# Mosfet_Driver_Circuit.net
KiCad netlist of a schematic drawn in Altium Designer
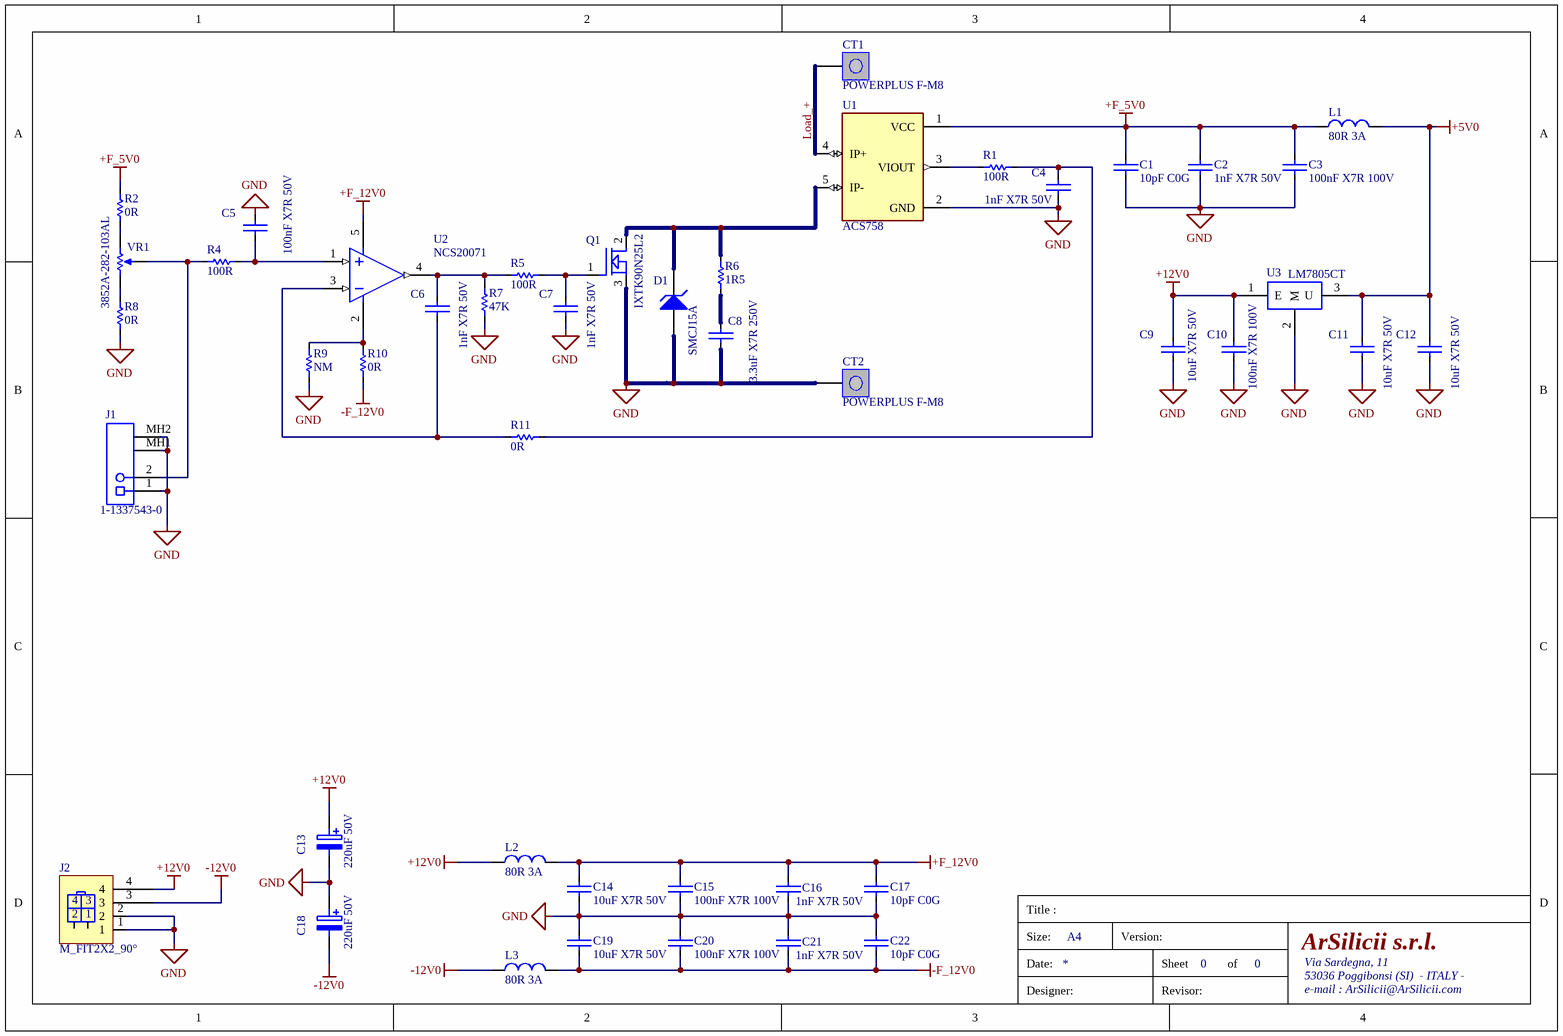
[diagram p0: Mosfet_Driver_Circuit.SchDoc]

(export (version "E")
  (design (tool "Eeschema 10.0.6"))
  (components
    (comp (ref "C1")
      (value "10pF C0G")
      (footprint "0805")
      (description "Capacità")
      (fields (field (name "ARSILICII PART NUMBER") "CPC0614010"))
      (libsource (lib "Library_20-02-20") (part "CAP_10pF C0G_0805"))
    )
    (comp (ref "C2")
      (value "1nF X7R 50V")
      (footprint "0805")
      (description "Capacità")
      (fields
        (field (name "1 SUPPLIER PART NUMBER") "B37941K5102K60")
        (field (name "2 SUPPLIER PART NUMBER") "0805B102K5CT")
      )
      (libsource (lib "Library_20-02-20") (part "CAP_1nF X7R 50V_0805"))
    )
    (comp (ref "C3")
      (value "100nF X7R 100V")
      (footprint "0805")
      (description "Capacità")
      (fields
        (field (name "1 SUPPLIER PART NUMBER") "CL21B104KCFSFNG")
        (field (name "2 SUPPLIER PART NUMBER") "1907331")
      )
      (libsource (lib "Library_20-02-20") (part "CAP_100nF X7R 100V_0805"))
    )
    (comp (ref "C4")
      (value "1nF X7R 50V")
      (footprint "0805")
      (description "Capacità")
      (fields
        (field (name "1 SUPPLIER PART NUMBER") "B37941K5102K60")
        (field (name "2 SUPPLIER PART NUMBER") "0805B102K5CT")
      )
      (libsource (lib "Library_20-02-20") (part "CAP_1nF X7R 50V_0805"))
    )
    (comp (ref "C5")
      (value "100nF X7R 50V")
      (footprint "0805")
      (description "Capacità")
      (fields
        (field (name "1 SUPPLIER PART NUMBER") "C0805C104K5RAC7800")
        (field (name "2 SUPPLIER PART NUMBER") "08055C104KAT2A AVX")
      )
      (libsource (lib "Library_20-02-20") (part "CAP_100nF X7R 50V_0805"))
    )
    (comp (ref "C6")
      (value "1nF X7R 50V")
      (footprint "0805")
      (description "Capacità")
      (fields
        (field (name "1 SUPPLIER PART NUMBER") "B37941K5102K60")
        (field (name "2 SUPPLIER PART NUMBER") "0805B102K5CT")
      )
      (libsource (lib "Library_20-02-20") (part "CAP_1nF X7R 50V_0805"))
    )
    (comp (ref "C7")
      (value "1nF X7R 50V")
      (footprint "0805")
      (description "Capacità")
      (fields
        (field (name "1 SUPPLIER PART NUMBER") "B37941K5102K60")
        (field (name "2 SUPPLIER PART NUMBER") "0805B102K5CT")
      )
      (libsource (lib "Library_20-02-20") (part "CAP_1nF X7R 50V_0805"))
    )
    (comp (ref "C8")
      (value "3.3uF X7R 250V")
      (footprint "2220")
      (description "Capacità")
      (fields
        (field (name "1 SUPPLIER PART NUMBER") "2435506")
        (field (name "2 SUPPLIER PART NUMBER") "810-CGA9N3X7R2E105K")
      )
      (libsource (lib "Library_20-02-20") (part "CAP_1uF X7R 250V_2220"))
    )
    (comp (ref "C9")
      (value "10uF X7R 50V")
      (footprint "1206")
      (description "Capacità")
      (fields
        (field (name "1 SUPPLIER PART NUMBER") "CL31B106KBHNNNE")
        (field (name "ARSILICII PART NUMBER") "CPC0232011")
      )
      (libsource (lib "Library_20-02-20") (part "CAP_10uF X7R 50V_1206"))
    )
    (comp (ref "C10")
      (value "100nF X7R 100V")
      (footprint "0805")
      (description "Capacità")
      (fields
        (field (name "1 SUPPLIER PART NUMBER") "CL21B104KCFSFNG")
        (field (name "2 SUPPLIER PART NUMBER") "1907331")
      )
      (libsource (lib "Library_20-02-20") (part "CAP_100nF X7R 100V_0805"))
    )
    (comp (ref "C11")
      (value "10uF X7R 50V")
      (footprint "1206")
      (description "Capacità")
      (fields
        (field (name "1 SUPPLIER PART NUMBER") "CL31B106KBHNNNE")
        (field (name "ARSILICII PART NUMBER") "CPC0232011")
      )
      (libsource (lib "Library_20-02-20") (part "CAP_10uF X7R 50V_1206"))
    )
    (comp (ref "C12")
      (value "10uF X7R 50V")
      (footprint "1206")
      (description "Capacità")
      (fields
        (field (name "1 SUPPLIER PART NUMBER") "CL31B106KBHNNNE")
        (field (name "ARSILICII PART NUMBER") "CPC0232011")
      )
      (libsource (lib "Library_20-02-20") (part "CAP_10uF X7R 50V_1206"))
    )
    (comp (ref "C13")
      (value "220uF 50V")
      (footprint "C_G55")
      (description "Capacità polarizzata")
      (fields
        (field (name "2 SUPPLIER PART NUMBER") "5194346")
        (field (name "ARSILICII PART NUMBER") "CPC0402221")
      )
      (libsource (lib "Library_20-02-20") (part "CAP_EL_220uF 50V"))
    )
    (comp (ref "C14")
      (value "10uF X7R 50V")
      (footprint "1206")
      (description "Capacità")
      (fields
        (field (name "1 SUPPLIER PART NUMBER") "CL31B106KBHNNNE")
        (field (name "ARSILICII PART NUMBER") "CPC0232011")
      )
      (libsource (lib "Library_20-02-20") (part "CAP_10uF X7R 50V_1206"))
    )
    (comp (ref "C15")
      (value "100nF X7R 100V")
      (footprint "0805")
      (description "Capacità")
      (fields
        (field (name "1 SUPPLIER PART NUMBER") "CL21B104KCFSFNG")
        (field (name "2 SUPPLIER PART NUMBER") "1907331")
      )
      (libsource (lib "Library_20-02-20") (part "CAP_100nF X7R 100V_0805"))
    )
    (comp (ref "C16")
      (value "1nF X7R 50V")
      (footprint "0805")
      (description "Capacità")
      (fields
        (field (name "1 SUPPLIER PART NUMBER") "B37941K5102K60")
        (field (name "2 SUPPLIER PART NUMBER") "0805B102K5CT")
      )
      (libsource (lib "Library_20-02-20") (part "CAP_1nF X7R 50V_0805"))
    )
    (comp (ref "C17")
      (value "10pF C0G")
      (footprint "0805")
      (description "Capacità")
      (fields (field (name "ARSILICII PART NUMBER") "CPC0614010"))
      (libsource (lib "Library_20-02-20") (part "CAP_10pF C0G_0805"))
    )
    (comp (ref "C18")
      (value "220uF 50V")
      (footprint "C_G55")
      (description "Capacità polarizzata")
      (fields
        (field (name "2 SUPPLIER PART NUMBER") "5194346")
        (field (name "ARSILICII PART NUMBER") "CPC0402221")
      )
      (libsource (lib "Library_20-02-20") (part "CAP_EL_220uF 50V"))
    )
    (comp (ref "C19")
      (value "10uF X7R 50V")
      (footprint "1206")
      (description "Capacità")
      (fields
        (field (name "1 SUPPLIER PART NUMBER") "CL31B106KBHNNNE")
        (field (name "ARSILICII PART NUMBER") "CPC0232011")
      )
      (libsource (lib "Library_20-02-20") (part "CAP_10uF X7R 50V_1206"))
    )
    (comp (ref "C20")
      (value "100nF X7R 100V")
      (footprint "0805")
      (description "Capacità")
      (fields
        (field (name "1 SUPPLIER PART NUMBER") "CL21B104KCFSFNG")
        (field (name "2 SUPPLIER PART NUMBER") "1907331")
      )
      (libsource (lib "Library_20-02-20") (part "CAP_100nF X7R 100V_0805"))
    )
    (comp (ref "C21")
      (value "1nF X7R 50V")
      (footprint "0805")
      (description "Capacità")
      (fields
        (field (name "1 SUPPLIER PART NUMBER") "B37941K5102K60")
        (field (name "2 SUPPLIER PART NUMBER") "0805B102K5CT")
      )
      (libsource (lib "Library_20-02-20") (part "CAP_1nF X7R 50V_0805"))
    )
    (comp (ref "C22")
      (value "10pF C0G")
      (footprint "0805")
      (description "Capacità")
      (fields (field (name "ARSILICII PART NUMBER") "CPC0614010"))
      (libsource (lib "Library_20-02-20") (part "CAP_10pF C0G_0805"))
    )
    (comp (ref "CT1")
      (value "POWERPLUS F-M8")
      (footprint "PowerPlus M8")
      (description "Singolo contatto")
      (fields
        (field (name "1 SUPPLIER PART NUMBER") "S98978")
        (field (name "ARSILICII PART NUMBER") "QC04000180")
      )
      (libsource (lib "Library_20-02-20") (part "PAD_POWERPLUS F-M8"))
    )
    (comp (ref "CT2")
      (value "POWERPLUS F-M8")
      (footprint "PowerPlus M8")
      (description "Singolo contatto")
      (fields
        (field (name "1 SUPPLIER PART NUMBER") "S98978")
        (field (name "ARSILICII PART NUMBER") "QC04000180")
      )
      (libsource (lib "Library_20-02-20") (part "PAD_POWERPLUS F-M8"))
    )
    (comp (ref "D1")
      (value "SMCJ15A")
      (footprint "LFUS-DO-214AB-2_V")
      (fields (field (name "MANUFACTURER") "Littelfuse"))
      (libsource (lib "Altium Content Vault") (part "DZEN-AK-2"))
    )
    (comp (ref "J1")
      (value "1-1337543-0")
      (footprint "TECO-1-1337543-0_V")
      (fields (field (name "MANUFACTURER") "TE Connectivity"))
      (libsource (lib "Altium Content Vault") (part "CN-1P-F-R2_A"))
    )
    (comp (ref "J2")
      (value "M_FIT2X2_90°")
      (footprint "M_FIT_JR2X2")
      (description "Mini Fit Junior 4 poli")
      (fields
        (field (name "3 SUPPLIER PART NUMBER") "C4255WR-2X2P")
        (field (name "ARSILICII PART NUMBER") "QA02001000")
      )
      (libsource (lib "ArS_Library") (part "M_FIT2X2_90°"))
    )
    (comp (ref "L1")
      (value "80R 3A")
      (footprint "1206")
      (description "Ferrite")
      (fields
        (field (name "1 SUPPLIER PART NUMBER") "3275550P")
        (field (name "ARSILICII PART NUMBER") "CPF0006000")
      )
      (libsource (lib "") (part "Ferrite 80R 3A_1"))
    )
    (comp (ref "L2")
      (value "80R 3A")
      (footprint "1206")
      (description "Ferrite")
      (fields
        (field (name "1 SUPPLIER PART NUMBER") "3275550P")
        (field (name "ARSILICII PART NUMBER") "CPF0006000")
      )
      (libsource (lib "Library_20-02-20") (part "Ferrite 80R 3A"))
    )
    (comp (ref "L3")
      (value "80R 3A")
      (footprint "1206")
      (description "Ferrite")
      (fields
        (field (name "1 SUPPLIER PART NUMBER") "3275550P")
        (field (name "ARSILICII PART NUMBER") "CPF0006000")
      )
      (libsource (lib "Library_20-02-20") (part "Ferrite 80R 3A"))
    )
    (comp (ref "Q1")
      (value "IXTK90N25L2")
      (footprint "Library_20-02-20:TO-247")
      (description "MOS CANALE N-250V-90A Linear")
      (fields
        (field (name "1 SUPPLIER PART NUMBER") "PB90N06S4-04")
        (field (name "2 SUPPLIER PART NUMBER") "826-9042P")
      )
      (libsource (lib "Library_20-02-20") (part "IXTK90N25L2"))
    )
    (comp (ref "R1")
      (value "100R")
      (footprint "0805")
      (description "Resistenza")
      (libsource (lib "Library_20-02-20") (part "RES_SMD"))
    )
    (comp (ref "R2")
      (value "0R")
      (footprint "0805")
      (description "Resistenza")
      (libsource (lib "Library_20-02-20") (part "RES_SMD"))
    )
    (comp (ref "R4")
      (value "100R")
      (footprint "0805")
      (description "Resistenza")
      (libsource (lib "Library_20-02-20") (part "RES_SMD"))
    )
    (comp (ref "R5")
      (value "100R")
      (footprint "0805")
      (description "Resistenza")
      (libsource (lib "Library_20-02-20") (part "RES_SMD"))
    )
    (comp (ref "R6")
      (value "1R5")
      (footprint "2512")
      (description "Resistenza")
      (libsource (lib "Library_20-02-20") (part "RES_SMD"))
    )
    (comp (ref "R7")
      (value "47K")
      (footprint "0805")
      (description "Resistenza")
      (libsource (lib "Library_20-02-20") (part "RES_SMD"))
    )
    (comp (ref "R8")
      (value "0R")
      (footprint "0805")
      (description "Resistenza")
      (libsource (lib "Library_20-02-20") (part "RES_SMD"))
    )
    (comp (ref "R9")
      (value "NM")
      (footprint "0805")
      (description "Resistenza")
      (libsource (lib "Library_20-02-20") (part "RES_SMD"))
    )
    (comp (ref "R10")
      (value "0R")
      (footprint "0805")
      (description "Resistenza")
      (libsource (lib "Library_20-02-20") (part "RES_SMD"))
    )
    (comp (ref "R11")
      (value "0R")
      (footprint "0805")
      (description "Resistenza")
      (libsource (lib "Library_20-02-20") (part "RES_SMD"))
    )
    (comp (ref "U1")
      (value "ACS758")
      (footprint "ArS_Library:XDCR_ACS758")
      (description "Current Sensor 50A 1 Channel Hall Effect, Open Loop Unidirectional 5-CB Formed Leads, PFF")
      (fields (field (name "MF") "Allegro MicroSystems LLC"))
      (libsource (lib "ArS_Library") (part "ACS758"))
    )
    (comp (ref "U2")
      (value "NCS20071")
      (footprint "SOT-553-5")
      (description "Rail-to-Rail Input/Output, 3 MHz Op Amps")
      (fields
        (field (name "1 SUPPLIER PART NUMBER") "MCP6021-E/SN-ND")
        (field (name "MANUFACTURER") "Microchip Technology")
      )
      (libsource (lib "Library_20-02-20") (part "NCS20071"))
    )
    (comp (ref "U3")
      (value "LM7805CT")
      (footprint "TO-220")
      (description "Stabilizzatore 5Volt 7805")
      (fields
        (field (name "ARSILICII PART NUMBER") "IC01007010")
        (field (name "MANUFACTURER") "Fairchild Semiconductor")
      )
      (libsource (lib "ArS_Library") (part "LM7805CT"))
    )
    (comp (ref "VR1")
      (value "3852A-282-103AL")
      (footprint "BOUR-3852A-282-103AL-3_V")
      (description "Diameter Panel Control, 10 KOhm, +/- 10%, 2 W, -1 to 125 degC, 3-Pin THD, RoHS, Bulk")
      (fields (field (name "TOLERANCE") "±10%") (field (name "MANUFACTURER") "Bourns"))
      (libsource (lib "Altium Content Vault") (part "RES-POT-3"))
    )
  )
  (nets
    (net (code "1") (name "+5V0") (class "Default")
      (node (ref "C11") (pin "1") (pintype "passive"))
      (node (ref "C12") (pin "1") (pintype "passive"))
      (node (ref "L1") (pin "1") (pinfunction "1_1") (pintype "passive"))
      (node (ref "U3") (pin "3") (pinfunction "U_3") (pintype "passive"))
    )
    (net (code "2") (name "+12V0") (class "Default")
      (node (ref "C10") (pin "1") (pintype "passive"))
      (node (ref "C13") (pin "1") (pintype "passive"))
      (node (ref "C9") (pin "1") (pintype "passive"))
      (node (ref "J2") (pin "4") (pinfunction "4_4") (pintype "passive"))
      (node (ref "L2") (pin "1") (pinfunction "1_1") (pintype "passive"))
      (node (ref "U3") (pin "1") (pinfunction "E_1") (pintype "passive"))
    )
    (net (code "3") (name "+F_5V0") (class "Default")
      (node (ref "C1") (pin "1") (pintype "passive"))
      (node (ref "C2") (pin "1") (pintype "passive"))
      (node (ref "C3") (pin "1") (pintype "passive"))
      (node (ref "L1") (pin "2") (pinfunction "2_2") (pintype "passive"))
      (node (ref "R2") (pin "2") (pinfunction "2_2") (pintype "passive"))
      (node (ref "U1") (pin "1") (pinfunction "VCC_1") (pintype "power_in"))
    )
    (net (code "4") (name "+F_12V0") (class "Default")
      (node (ref "C14") (pin "1") (pintype "passive"))
      (node (ref "C15") (pin "1") (pintype "passive"))
      (node (ref "C16") (pin "1") (pintype "passive"))
      (node (ref "C17") (pin "1") (pintype "passive"))
      (node (ref "L2") (pin "2") (pinfunction "2_2") (pintype "passive"))
      (node (ref "U2") (pin "5") (pintype "power_in"))
    )
    (net (code "5") (name "-12V0") (class "Default")
      (node (ref "C18") (pin "2") (pintype "passive"))
      (node (ref "J2") (pin "3") (pinfunction "3_3") (pintype "passive"))
      (node (ref "L3") (pin "1") (pinfunction "1_1") (pintype "passive"))
    )
    (net (code "6") (name "-F_12V0") (class "Default")
      (node (ref "C19") (pin "2") (pintype "passive"))
      (node (ref "C20") (pin "2") (pintype "passive"))
      (node (ref "C21") (pin "2") (pintype "passive"))
      (node (ref "C22") (pin "2") (pintype "passive"))
      (node (ref "L3") (pin "2") (pinfunction "2_2") (pintype "passive"))
      (node (ref "R10") (pin "1") (pinfunction "1_1") (pintype "passive"))
    )
    (net (code "7") (name "/Load_+") (class "Default")
      (node (ref "CT1") (pin "1") (pinfunction "1_1") (pintype "passive"))
      (node (ref "U1") (pin "4") (pinfunction "IP+_4") (pintype "bidirectional"))
    )
    (net (code "8") (name "GND") (class "Default")
      (node (ref "C1") (pin "2") (pintype "passive"))
      (node (ref "C10") (pin "2") (pintype "passive"))
      (node (ref "C11") (pin "2") (pintype "passive"))
      (node (ref "C12") (pin "2") (pintype "passive"))
      (node (ref "C13") (pin "2") (pintype "passive"))
      (node (ref "C14") (pin "2") (pintype "passive"))
      (node (ref "C15") (pin "2") (pintype "passive"))
      (node (ref "C16") (pin "2") (pintype "passive"))
      (node (ref "C17") (pin "2") (pintype "passive"))
      (node (ref "C18") (pin "1") (pintype "passive"))
      (node (ref "C19") (pin "1") (pintype "passive"))
      (node (ref "C2") (pin "2") (pintype "passive"))
      (node (ref "C20") (pin "1") (pintype "passive"))
      (node (ref "C21") (pin "1") (pintype "passive"))
      (node (ref "C22") (pin "1") (pintype "passive"))
      (node (ref "C3") (pin "2") (pintype "passive"))
      (node (ref "C4") (pin "2") (pintype "passive"))
      (node (ref "C5") (pin "1") (pintype "passive"))
      (node (ref "C7") (pin "2") (pintype "passive"))
      (node (ref "C8") (pin "2") (pintype "passive"))
      (node (ref "C9") (pin "2") (pintype "passive"))
      (node (ref "CT2") (pin "1") (pinfunction "1_1") (pintype "passive"))
      (node (ref "D1") (pin "1") (pinfunction "A_1") (pintype "passive"))
      (node (ref "J1") (pin "1") (pinfunction "1_1") (pintype "passive"))
      (node (ref "J1") (pin "MH1") (pinfunction "MH1_MH1") (pintype "passive"))
      (node (ref "J1") (pin "MH2") (pinfunction "MH2_MH2") (pintype "passive"))
      (node (ref "J2") (pin "1") (pinfunction "1_1") (pintype "passive"))
      (node (ref "J2") (pin "2") (pinfunction "2_2") (pintype "passive"))
      (node (ref "Q1") (pin "3") (pinfunction "SOURCE_3") (pintype "passive"))
      (node (ref "R7") (pin "2") (pinfunction "2_2") (pintype "passive"))
      (node (ref "R8") (pin "1") (pinfunction "1_1") (pintype "passive"))
      (node (ref "R9") (pin "1") (pinfunction "1_1") (pintype "passive"))
      (node (ref "U1") (pin "2") (pinfunction "GND_2") (pintype "power_in"))
      (node (ref "U3") (pin "2") (pinfunction "M_2") (pintype "passive"))
    )
    (net (code "9") (name "Net-(C4-Pad1)") (class "Default")
      (node (ref "C4") (pin "1") (pintype "passive"))
      (node (ref "R1") (pin "2") (pinfunction "2_2") (pintype "passive"))
      (node (ref "R11") (pin "2") (pinfunction "2_2") (pintype "passive"))
    )
    (net (code "10") (name "Net-(C5-Pad2)") (class "Default")
      (node (ref "C5") (pin "2") (pintype "passive"))
      (node (ref "R4") (pin "2") (pinfunction "2_2") (pintype "passive"))
      (node (ref "U2") (pin "1") (pintype "input"))
    )
    (net (code "11") (name "Net-(C6-Pad1)") (class "Default")
      (node (ref "C6") (pin "1") (pintype "passive"))
      (node (ref "R5") (pin "1") (pinfunction "1_1") (pintype "passive"))
      (node (ref "R7") (pin "1") (pinfunction "1_1") (pintype "passive"))
      (node (ref "U2") (pin "4") (pintype "output"))
    )
    (net (code "12") (name "Net-(C6-Pad2)") (class "Default")
      (node (ref "C6") (pin "2") (pintype "passive"))
      (node (ref "R11") (pin "1") (pinfunction "1_1") (pintype "passive"))
      (node (ref "U2") (pin "3") (pintype "input"))
    )
    (net (code "13") (name "Net-(C8-Pad1)") (class "Default")
      (node (ref "C8") (pin "1") (pintype "passive"))
      (node (ref "R6") (pin "2") (pinfunction "2_2") (pintype "passive"))
    )
    (net (code "14") (name "Net-(D1-K)") (class "Default")
      (node (ref "D1") (pin "2") (pinfunction "K_2") (pintype "passive"))
      (node (ref "Q1") (pin "2") (pinfunction "DRAIN_2") (pintype "passive"))
      (node (ref "R6") (pin "1") (pinfunction "1_1") (pintype "passive"))
      (node (ref "U1") (pin "5") (pinfunction "IP-_5") (pintype "bidirectional"))
    )
    (net (code "15") (name "Net-(Q1-GATE)") (class "Default")
      (node (ref "C7") (pin "1") (pintype "passive"))
      (node (ref "Q1") (pin "1") (pinfunction "GATE_1") (pintype "passive"))
      (node (ref "R5") (pin "2") (pinfunction "2_2") (pintype "passive"))
    )
    (net (code "16") (name "Net-(R10-Pad2)") (class "Default")
      (node (ref "R10") (pin "2") (pinfunction "2_2") (pintype "passive"))
      (node (ref "R9") (pin "2") (pinfunction "2_2") (pintype "passive"))
      (node (ref "U2") (pin "2") (pintype "power_in"))
    )
    (net (code "17") (name "Net-(U1-VIOUT)") (class "Default")
      (node (ref "R1") (pin "1") (pinfunction "1_1") (pintype "passive"))
      (node (ref "U1") (pin "3") (pinfunction "VIOUT_3") (pintype "output"))
    )
    (net (code "18") (name "Net-(VR1-CCW)") (class "Default")
      (node (ref "R8") (pin "2") (pinfunction "2_2") (pintype "passive"))
      (node (ref "VR1") (pin "1") (pinfunction "CCW_1") (pintype "passive"))
    )
    (net (code "19") (name "Net-(VR1-CW)") (class "Default")
      (node (ref "R2") (pin "1") (pinfunction "1_1") (pintype "passive"))
      (node (ref "VR1") (pin "3") (pinfunction "CW_3") (pintype "passive"))
    )
    (net (code "20") (name "Net-(VR1-S)") (class "Default")
      (node (ref "J1") (pin "2") (pinfunction "2_2") (pintype "passive"))
      (node (ref "R4") (pin "1") (pinfunction "1_1") (pintype "passive"))
      (node (ref "VR1") (pin "2") (pinfunction "S_2") (pintype "passive"))
    )
  )
)
